# 04_ANALOG_B.net
KiCad netlist of a schematic drawn in Altium Designer
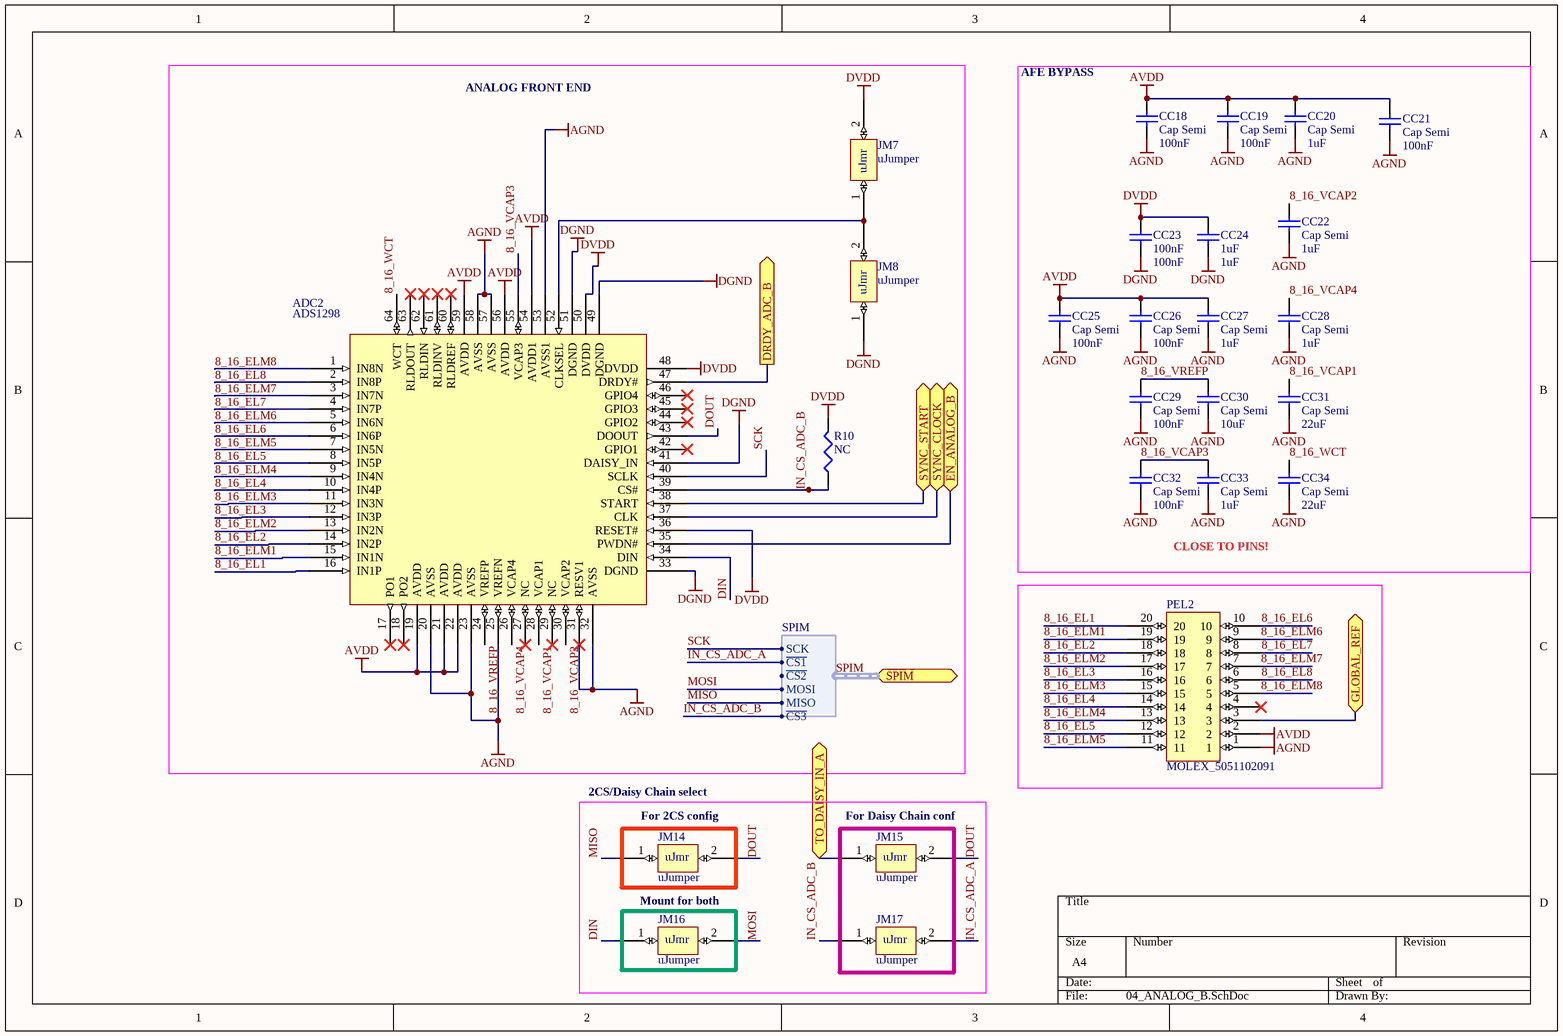
[diagram p0: 04_ANALOG_B.SchDoc]

(export (version "E")
  (design (tool "Eeschema 10.0.6"))
  (components
    (comp (ref "ADC2")
      (value "ADS1298")
      (footprint "Demo_Board_library_PCB:S-PQFP - G64 - ADS1298")
      (libsource (lib "Schlib1") (part "ADS1298"))
    )
    (comp (ref "CC18")
      (value "Cap Semi")
      (footprint "0402")
      (description "Capacitor (Semiconductor SIM Model)")
      (fields (field (name "ALTIUM_VALUE") "100nF") (field (name "PUBLISHER") "Altium Limited"))
      (libsource (lib "Miscellaneous Devices") (part "Cap Semi"))
    )
    (comp (ref "CC19")
      (value "Cap Semi")
      (footprint "0402")
      (description "Capacitor (Semiconductor SIM Model)")
      (fields (field (name "ALTIUM_VALUE") "100nF") (field (name "PUBLISHER") "Altium Limited"))
      (libsource (lib "Miscellaneous Devices") (part "Cap Semi"))
    )
    (comp (ref "CC20")
      (value "Cap Semi")
      (footprint "0402")
      (description "Capacitor (Semiconductor SIM Model)")
      (fields (field (name "ALTIUM_VALUE") "1uF") (field (name "PUBLISHER") "Altium Limited"))
      (libsource (lib "Miscellaneous Devices") (part "Cap Semi"))
    )
    (comp (ref "CC21")
      (value "Cap Semi")
      (footprint "0402")
      (description "Capacitor (Semiconductor SIM Model)")
      (fields (field (name "ALTIUM_VALUE") "100nF") (field (name "PUBLISHER") "Altium Limited"))
      (libsource (lib "Miscellaneous Devices") (part "Cap Semi"))
    )
    (comp (ref "CC22")
      (value "Cap Semi")
      (footprint "0402")
      (description "Capacitor (Semiconductor SIM Model)")
      (fields (field (name "ALTIUM_VALUE") "1uF") (field (name "PUBLISHER") "Altium Limited"))
      (libsource (lib "Miscellaneous Devices") (part "Cap Semi"))
    )
    (comp (ref "CC23")
      (value "100nF")
      (footprint "0402")
      (description "Capacitor (Semiconductor SIM Model)")
      (fields (field (name "ALTIUM_VALUE") "100nF") (field (name "PUBLISHER") "Altium Limited"))
      (libsource (lib "Miscellaneous Devices") (part "Cap Semi"))
    )
    (comp (ref "CC24")
      (value "1uF")
      (footprint "0402")
      (description "Capacitor (Semiconductor SIM Model)")
      (fields (field (name "ALTIUM_VALUE") "1uF") (field (name "PUBLISHER") "Altium Limited"))
      (libsource (lib "Miscellaneous Devices") (part "Cap Semi"))
    )
    (comp (ref "CC25")
      (value "Cap Semi")
      (footprint "0402")
      (description "Capacitor (Semiconductor SIM Model)")
      (fields (field (name "ALTIUM_VALUE") "100nF") (field (name "PUBLISHER") "Altium Limited"))
      (libsource (lib "Miscellaneous Devices") (part "Cap Semi"))
    )
    (comp (ref "CC26")
      (value "Cap Semi")
      (footprint "0402")
      (description "Capacitor (Semiconductor SIM Model)")
      (fields (field (name "ALTIUM_VALUE") "100nF") (field (name "PUBLISHER") "Altium Limited"))
      (libsource (lib "Miscellaneous Devices") (part "Cap Semi"))
    )
    (comp (ref "CC27")
      (value "Cap Semi")
      (footprint "0402")
      (description "Capacitor (Semiconductor SIM Model)")
      (fields (field (name "ALTIUM_VALUE") "1uF") (field (name "PUBLISHER") "Altium Limited"))
      (libsource (lib "Miscellaneous Devices") (part "Cap Semi"))
    )
    (comp (ref "CC28")
      (value "Cap Semi")
      (footprint "0402")
      (description "Capacitor (Semiconductor SIM Model)")
      (fields (field (name "ALTIUM_VALUE") "1uF") (field (name "PUBLISHER") "Altium Limited"))
      (libsource (lib "Miscellaneous Devices") (part "Cap Semi"))
    )
    (comp (ref "CC29")
      (value "Cap Semi")
      (footprint "0402")
      (description "Capacitor (Semiconductor SIM Model)")
      (fields (field (name "ALTIUM_VALUE") "100nF") (field (name "PUBLISHER") "Altium Limited"))
      (libsource (lib "Miscellaneous Devices") (part "Cap Semi"))
    )
    (comp (ref "CC30")
      (value "Cap Semi")
      (footprint "0402")
      (description "Capacitor (Semiconductor SIM Model)")
      (fields (field (name "ALTIUM_VALUE") "10uF") (field (name "PUBLISHER") "Altium Limited"))
      (libsource (lib "Miscellaneous Devices") (part "Cap Semi"))
    )
    (comp (ref "CC31")
      (value "Cap Semi")
      (footprint "J1-0603")
      (description "Capacitor (Semiconductor SIM Model)")
      (fields (field (name "ALTIUM_VALUE") "22uF") (field (name "PUBLISHER") "Altium Limited"))
      (libsource (lib "Miscellaneous Devices") (part "Cap Semi"))
    )
    (comp (ref "CC32")
      (value "Cap Semi")
      (footprint "0402")
      (description "Capacitor (Semiconductor SIM Model)")
      (fields (field (name "ALTIUM_VALUE") "100nF") (field (name "PUBLISHER") "Altium Limited"))
      (libsource (lib "Miscellaneous Devices") (part "Cap Semi"))
    )
    (comp (ref "CC33")
      (value "Cap Semi")
      (footprint "0402")
      (description "Capacitor (Semiconductor SIM Model)")
      (fields (field (name "ALTIUM_VALUE") "1uF") (field (name "PUBLISHER") "Altium Limited"))
      (libsource (lib "Miscellaneous Devices") (part "Cap Semi"))
    )
    (comp (ref "CC34")
      (value "Cap Semi")
      (footprint "1608[0603]")
      (description "Capacitor (Semiconductor SIM Model)")
      (fields (field (name "ALTIUM_VALUE") "22uF") (field (name "PUBLISHER") "Altium Limited"))
      (libsource (lib "Miscellaneous Devices") (part "Cap Semi"))
    )
    (comp (ref "JM7") (value "uJumper") (footprint "UJMPR") (libsource (lib "Schlib1") (part "uJumper")))
    (comp (ref "JM8") (value "uJumper") (footprint "UJMPR") (libsource (lib "Schlib1") (part "uJumper")))
    (comp (ref "JM14") (value "uJumper") (footprint "UJMPR") (libsource (lib "") (part "uJumper_1")))
    (comp (ref "JM15") (value "uJumper") (footprint "UJMPR") (libsource (lib "") (part "uJumper_1")))
    (comp (ref "JM16") (value "uJumper") (footprint "UJMPR") (libsource (lib "") (part "uJumper_1")))
    (comp (ref "JM17") (value "uJumper") (footprint "UJMPR") (libsource (lib "") (part "uJumper_1")))
    (comp (ref "PEL2")
      (value "MOLEX_5051102091")
      (footprint "MOLEX_5051102091")
      (libsource (lib "Schlib1") (part "MOLEX_5051102091"))
    )
    (comp (ref "R10")
      (value "NC")
      (footprint "0402")
      (description "Resistor")
      (fields (field (name "PUBLISHER") "Altium Limited"))
      (libsource (lib "Miscellaneous Devices") (part "Res3"))
    )
  )
  (nets
    (net (code "2") (name "/8_16_EL1") (class "Default")
      (node (ref "ADC2") (pin "16") (pinfunction "IN1P_16") (pintype "input"))
      (node (ref "PEL2") (pin "20") (pinfunction "20_20") (pintype "bidirectional"))
    )
    (net (code "3") (name "/8_16_EL2") (class "Default")
      (node (ref "ADC2") (pin "14") (pinfunction "IN2P_14") (pintype "input"))
      (node (ref "PEL2") (pin "18") (pinfunction "18_18") (pintype "bidirectional"))
    )
    (net (code "4") (name "/8_16_EL3") (class "Default")
      (node (ref "ADC2") (pin "12") (pinfunction "IN3P_12") (pintype "input"))
      (node (ref "PEL2") (pin "16") (pinfunction "16_16") (pintype "bidirectional"))
    )
    (net (code "5") (name "/8_16_EL4") (class "Default")
      (node (ref "ADC2") (pin "10") (pinfunction "IN4P_10") (pintype "input"))
      (node (ref "PEL2") (pin "14") (pinfunction "14_14") (pintype "bidirectional"))
    )
    (net (code "6") (name "/8_16_EL5") (class "Default")
      (node (ref "ADC2") (pin "8") (pinfunction "IN5P_8") (pintype "input"))
      (node (ref "PEL2") (pin "12") (pinfunction "12_12") (pintype "bidirectional"))
    )
    (net (code "7") (name "/8_16_EL6") (class "Default")
      (node (ref "ADC2") (pin "6") (pinfunction "IN6P_6") (pintype "input"))
      (node (ref "PEL2") (pin "10") (pinfunction "10_10") (pintype "bidirectional"))
    )
    (net (code "8") (name "/8_16_EL7") (class "Default")
      (node (ref "ADC2") (pin "4") (pinfunction "IN7P_4") (pintype "input"))
      (node (ref "PEL2") (pin "8") (pinfunction "8_8") (pintype "bidirectional"))
    )
    (net (code "9") (name "/8_16_EL8") (class "Default")
      (node (ref "ADC2") (pin "2") (pinfunction "IN8P_2") (pintype "input"))
      (node (ref "PEL2") (pin "6") (pinfunction "6_6") (pintype "bidirectional"))
    )
    (net (code "10") (name "/8_16_ELM1") (class "Default")
      (node (ref "ADC2") (pin "15") (pinfunction "IN1N_15") (pintype "input"))
      (node (ref "PEL2") (pin "19") (pinfunction "19_19") (pintype "bidirectional"))
    )
    (net (code "11") (name "/8_16_ELM2") (class "Default")
      (node (ref "ADC2") (pin "13") (pinfunction "IN2N_13") (pintype "input"))
      (node (ref "PEL2") (pin "17") (pinfunction "17_17") (pintype "bidirectional"))
    )
    (net (code "12") (name "/8_16_ELM3") (class "Default")
      (node (ref "ADC2") (pin "11") (pinfunction "IN3N_11") (pintype "input"))
      (node (ref "PEL2") (pin "15") (pinfunction "15_15") (pintype "bidirectional"))
    )
    (net (code "13") (name "/8_16_ELM4") (class "Default")
      (node (ref "ADC2") (pin "9") (pinfunction "IN4N_9") (pintype "input"))
      (node (ref "PEL2") (pin "13") (pinfunction "13_13") (pintype "bidirectional"))
    )
    (net (code "14") (name "/8_16_ELM5") (class "Default")
      (node (ref "ADC2") (pin "7") (pinfunction "IN5N_7") (pintype "input"))
      (node (ref "PEL2") (pin "11") (pinfunction "11_11") (pintype "bidirectional"))
    )
    (net (code "15") (name "/8_16_ELM6") (class "Default")
      (node (ref "ADC2") (pin "5") (pinfunction "IN6N_5") (pintype "input"))
      (node (ref "PEL2") (pin "9") (pinfunction "9_9") (pintype "bidirectional"))
    )
    (net (code "16") (name "/8_16_ELM7") (class "Default")
      (node (ref "ADC2") (pin "3") (pinfunction "IN7N_3") (pintype "input"))
      (node (ref "PEL2") (pin "7") (pinfunction "7_7") (pintype "bidirectional"))
    )
    (net (code "17") (name "/8_16_ELM8") (class "Default")
      (node (ref "ADC2") (pin "1") (pinfunction "IN8N_1") (pintype "input"))
      (node (ref "PEL2") (pin "5") (pinfunction "5_5") (pintype "bidirectional"))
    )
    (net (code "18") (name "/8_16_VCAP1") (class "Default")
      (node (ref "ADC2") (pin "28") (pinfunction "VCAP1_28") (pintype "bidirectional"))
      (node (ref "CC31") (pin "2") (pinfunction "2_2") (pintype "passive"))
    )
    (net (code "19") (name "/8_16_VCAP2") (class "Default")
      (node (ref "ADC2") (pin "30") (pinfunction "VCAP2_30") (pintype "bidirectional"))
      (node (ref "CC22") (pin "2") (pinfunction "2_2") (pintype "passive"))
    )
    (net (code "20") (name "/8_16_VCAP3") (class "Default")
      (node (ref "ADC2") (pin "55") (pinfunction "VCAP3_55") (pintype "bidirectional"))
      (node (ref "CC32") (pin "2") (pinfunction "2_2") (pintype "passive"))
      (node (ref "CC33") (pin "2") (pinfunction "2_2") (pintype "passive"))
    )
    (net (code "21") (name "/8_16_VCAP4") (class "Default")
      (node (ref "ADC2") (pin "26") (pinfunction "VCAP4_26") (pintype "bidirectional"))
      (node (ref "CC28") (pin "2") (pinfunction "2_2") (pintype "passive"))
    )
    (net (code "22") (name "/8_16_VREFP") (class "Default")
      (node (ref "ADC2") (pin "24") (pinfunction "VREFP_24") (pintype "bidirectional"))
      (node (ref "CC29") (pin "2") (pinfunction "2_2") (pintype "passive"))
      (node (ref "CC30") (pin "2") (pinfunction "2_2") (pintype "passive"))
    )
    (net (code "23") (name "/8_16_WCT") (class "Default")
      (node (ref "ADC2") (pin "64") (pinfunction "WCT_64") (pintype "bidirectional"))
      (node (ref "CC34") (pin "2") (pinfunction "2_2") (pintype "passive"))
    )
    (net (code "24") (name "/DIN") (class "Default")
      (node (ref "ADC2") (pin "34") (pinfunction "DIN_34") (pintype "input"))
      (node (ref "JM16") (pin "1") (pintype "bidirectional"))
    )
    (net (code "25") (name "/DOUT") (class "Default")
      (node (ref "ADC2") (pin "43") (pinfunction "DOOUT_43") (pintype "output"))
      (node (ref "JM14") (pin "2") (pintype "bidirectional"))
      (node (ref "JM15") (pin "2") (pintype "bidirectional"))
    )
    (net (code "26") (name "/DRDY_ADC_B") (class "Default")
      (node (ref "ADC2") (pin "47") (pinfunction "DRDY#_47") (pintype "output"))
    )
    (net (code "27") (name "/EN_ANALOG_B") (class "Default")
      (node (ref "ADC2") (pin "35") (pinfunction "PWDN#_35") (pintype "input"))
    )
    (net (code "28") (name "/GLOBAL_REF") (class "Default")
      (node (ref "PEL2") (pin "3") (pinfunction "3_3") (pintype "bidirectional"))
    )
    (net (code "29") (name "/IN_CS_ADC_A") (class "Default")
      (node (ref "JM17") (pin "2") (pintype "bidirectional"))
    )
    (net (code "30") (name "/IN_CS_ADC_B") (class "Default")
      (node (ref "ADC2") (pin "39") (pinfunction "CS#_39") (pintype "input"))
      (node (ref "JM17") (pin "1") (pintype "bidirectional"))
      (node (ref "R10") (pin "1") (pinfunction "1_1") (pintype "passive"))
    )
    (net (code "31") (name "/MISO") (class "Default") (node (ref "JM14") (pin "1") (pintype "bidirectional")))
    (net (code "32") (name "/MOSI") (class "Default") (node (ref "JM16") (pin "2") (pintype "bidirectional")))
    (net (code "33") (name "/SCK") (class "Default")
      (node (ref "ADC2") (pin "40") (pinfunction "SCLK_40") (pintype "input"))
    )
    (net (code "35") (name "/SYNC_CLOCK") (class "Default")
      (node (ref "ADC2") (pin "37") (pinfunction "CLK_37") (pintype "input"))
    )
    (net (code "36") (name "/SYNC_START") (class "Default")
      (node (ref "ADC2") (pin "38") (pinfunction "START_38") (pintype "input"))
    )
    (net (code "37") (name "/TO_DAISY_IN_A") (class "Default")
      (node (ref "JM15") (pin "1") (pintype "bidirectional"))
    )
    (net (code "38") (name "AGND") (class "Default")
      (node (ref "ADC2") (pin "20") (pinfunction "AVSS_20") (pintype "power_in"))
      (node (ref "ADC2") (pin "23") (pinfunction "AVSS_23") (pintype "power_in"))
      (node (ref "ADC2") (pin "25") (pinfunction "VREFN_25") (pintype "bidirectional"))
      (node (ref "ADC2") (pin "31") (pinfunction "RESV1_31") (pintype "bidirectional"))
      (node (ref "ADC2") (pin "32") (pinfunction "AVSS_32") (pintype "power_in"))
      (node (ref "ADC2") (pin "53") (pinfunction "AVSS1_53") (pintype "power_in"))
      (node (ref "ADC2") (pin "57") (pinfunction "AVSS_57") (pintype "power_in"))
      (node (ref "ADC2") (pin "58") (pinfunction "AVSS_58") (pintype "power_in"))
      (node (ref "CC18") (pin "1") (pinfunction "1_1") (pintype "passive"))
      (node (ref "CC19") (pin "1") (pinfunction "1_1") (pintype "passive"))
      (node (ref "CC20") (pin "1") (pinfunction "1_1") (pintype "passive"))
      (node (ref "CC21") (pin "1") (pinfunction "1_1") (pintype "passive"))
      (node (ref "CC22") (pin "1") (pinfunction "1_1") (pintype "passive"))
      (node (ref "CC25") (pin "1") (pinfunction "1_1") (pintype "passive"))
      (node (ref "CC26") (pin "1") (pinfunction "1_1") (pintype "passive"))
      (node (ref "CC27") (pin "1") (pinfunction "1_1") (pintype "passive"))
      (node (ref "CC28") (pin "1") (pinfunction "1_1") (pintype "passive"))
      (node (ref "CC29") (pin "1") (pinfunction "1_1") (pintype "passive"))
      (node (ref "CC30") (pin "1") (pinfunction "1_1") (pintype "passive"))
      (node (ref "CC31") (pin "1") (pinfunction "1_1") (pintype "passive"))
      (node (ref "CC32") (pin "1") (pinfunction "1_1") (pintype "passive"))
      (node (ref "CC33") (pin "1") (pinfunction "1_1") (pintype "passive"))
      (node (ref "CC34") (pin "1") (pinfunction "1_1") (pintype "passive"))
      (node (ref "PEL2") (pin "1") (pinfunction "1_1") (pintype "bidirectional"))
    )
    (net (code "39") (name "AVDD") (class "Default")
      (node (ref "ADC2") (pin "19") (pinfunction "AVDD_19") (pintype "power_in"))
      (node (ref "ADC2") (pin "21") (pinfunction "AVDD_21") (pintype "power_in"))
      (node (ref "ADC2") (pin "22") (pinfunction "AVDD_22") (pintype "power_in"))
      (node (ref "ADC2") (pin "54") (pinfunction "AVDD1_54") (pintype "power_in"))
      (node (ref "ADC2") (pin "56") (pinfunction "AVDD_56") (pintype "power_in"))
      (node (ref "ADC2") (pin "59") (pinfunction "AVDD_59") (pintype "power_in"))
      (node (ref "CC18") (pin "2") (pinfunction "2_2") (pintype "passive"))
      (node (ref "CC19") (pin "2") (pinfunction "2_2") (pintype "passive"))
      (node (ref "CC20") (pin "2") (pinfunction "2_2") (pintype "passive"))
      (node (ref "CC21") (pin "2") (pinfunction "2_2") (pintype "passive"))
      (node (ref "CC25") (pin "2") (pinfunction "2_2") (pintype "passive"))
      (node (ref "CC26") (pin "2") (pinfunction "2_2") (pintype "passive"))
      (node (ref "CC27") (pin "2") (pinfunction "2_2") (pintype "passive"))
      (node (ref "PEL2") (pin "2") (pinfunction "2_2") (pintype "bidirectional"))
    )
    (net (code "40") (name "DGND") (class "Default")
      (node (ref "ADC2") (pin "33") (pinfunction "DGND_33") (pintype "power_in"))
      (node (ref "ADC2") (pin "41") (pinfunction "DAISY_IN_41") (pintype "input"))
      (node (ref "ADC2") (pin "49") (pinfunction "DGND_49") (pintype "power_in"))
      (node (ref "ADC2") (pin "51") (pinfunction "DGND_51") (pintype "power_in"))
      (node (ref "CC23") (pin "1") (pinfunction "1_1") (pintype "passive"))
      (node (ref "CC24") (pin "1") (pinfunction "1_1") (pintype "passive"))
      (node (ref "JM8") (pin "1") (pintype "bidirectional"))
    )
    (net (code "41") (name "DVDD") (class "Default")
      (node (ref "ADC2") (pin "36") (pinfunction "RESET#_36") (pintype "input"))
      (node (ref "ADC2") (pin "48") (pinfunction "DVDD_48") (pintype "power_in"))
      (node (ref "ADC2") (pin "50") (pinfunction "DVDD_50") (pintype "power_in"))
      (node (ref "CC23") (pin "2") (pinfunction "2_2") (pintype "passive"))
      (node (ref "CC24") (pin "2") (pinfunction "2_2") (pintype "passive"))
      (node (ref "JM7") (pin "2") (pintype "bidirectional"))
      (node (ref "R10") (pin "2") (pinfunction "2_2") (pintype "passive"))
    )
    (net (code "42") (name "Net-(ADC2-CLKSEL)") (class "Default")
      (node (ref "ADC2") (pin "52") (pinfunction "CLKSEL_52") (pintype "input"))
      (node (ref "JM7") (pin "1") (pintype "bidirectional"))
      (node (ref "JM8") (pin "2") (pintype "bidirectional"))
    )
    (net (code "43") (name "unconnected-(ADC2-GPIO1-Pad42)") (class "Default")
      (node (ref "ADC2") (pin "42") (pinfunction "GPIO1_42") (pintype "bidirectional+no_connect"))
    )
    (net (code "44") (name "unconnected-(ADC2-GPIO2-Pad44)") (class "Default")
      (node (ref "ADC2") (pin "44") (pinfunction "GPIO2_44") (pintype "bidirectional+no_connect"))
    )
    (net (code "45") (name "unconnected-(ADC2-GPIO3-Pad45)") (class "Default")
      (node (ref "ADC2") (pin "45") (pinfunction "GPIO3_45") (pintype "bidirectional+no_connect"))
    )
    (net (code "46") (name "unconnected-(ADC2-GPIO4-Pad46)") (class "Default")
      (node (ref "ADC2") (pin "46") (pinfunction "GPIO4_46") (pintype "bidirectional+no_connect"))
    )
    (net (code "47") (name "unconnected-(ADC2-NC-Pad27)") (class "Default")
      (node (ref "ADC2") (pin "27") (pinfunction "NC_27") (pintype "bidirectional+no_connect"))
    )
    (net (code "48") (name "unconnected-(ADC2-NC-Pad29)") (class "Default")
      (node (ref "ADC2") (pin "29") (pinfunction "NC_29") (pintype "bidirectional+no_connect"))
    )
    (net (code "49") (name "unconnected-(ADC2-PO1-Pad17)") (class "Default")
      (node (ref "ADC2") (pin "17") (pinfunction "PO1_17") (pintype "output+no_connect"))
    )
    (net (code "50") (name "unconnected-(ADC2-PO2-Pad18)") (class "Default")
      (node (ref "ADC2") (pin "18") (pinfunction "PO2_18") (pintype "output+no_connect"))
    )
    (net (code "51") (name "unconnected-(ADC2-RLDIN-Pad62)") (class "Default")
      (node (ref "ADC2") (pin "62") (pinfunction "RLDIN_62") (pintype "input+no_connect"))
    )
    (net (code "52") (name "unconnected-(ADC2-RLDINV-Pad61)") (class "Default")
      (node (ref "ADC2") (pin "61") (pinfunction "RLDINV_61") (pintype "bidirectional+no_connect"))
    )
    (net (code "53") (name "unconnected-(ADC2-RLDOUT-Pad63)") (class "Default")
      (node (ref "ADC2") (pin "63") (pinfunction "RLDOUT_63") (pintype "output+no_connect"))
    )
    (net (code "54") (name "unconnected-(ADC2-RLDREF-Pad60)") (class "Default")
      (node (ref "ADC2") (pin "60") (pinfunction "RLDREF_60") (pintype "bidirectional+no_connect"))
    )
    (net (code "55") (name "unconnected-(PEL2-Pad4)") (class "Default")
      (node (ref "PEL2") (pin "4") (pinfunction "4_4") (pintype "bidirectional+no_connect"))
    )
  )
)
